# Communication_Connectors.net
KiCad netlist of a schematic drawn in Altium Designer
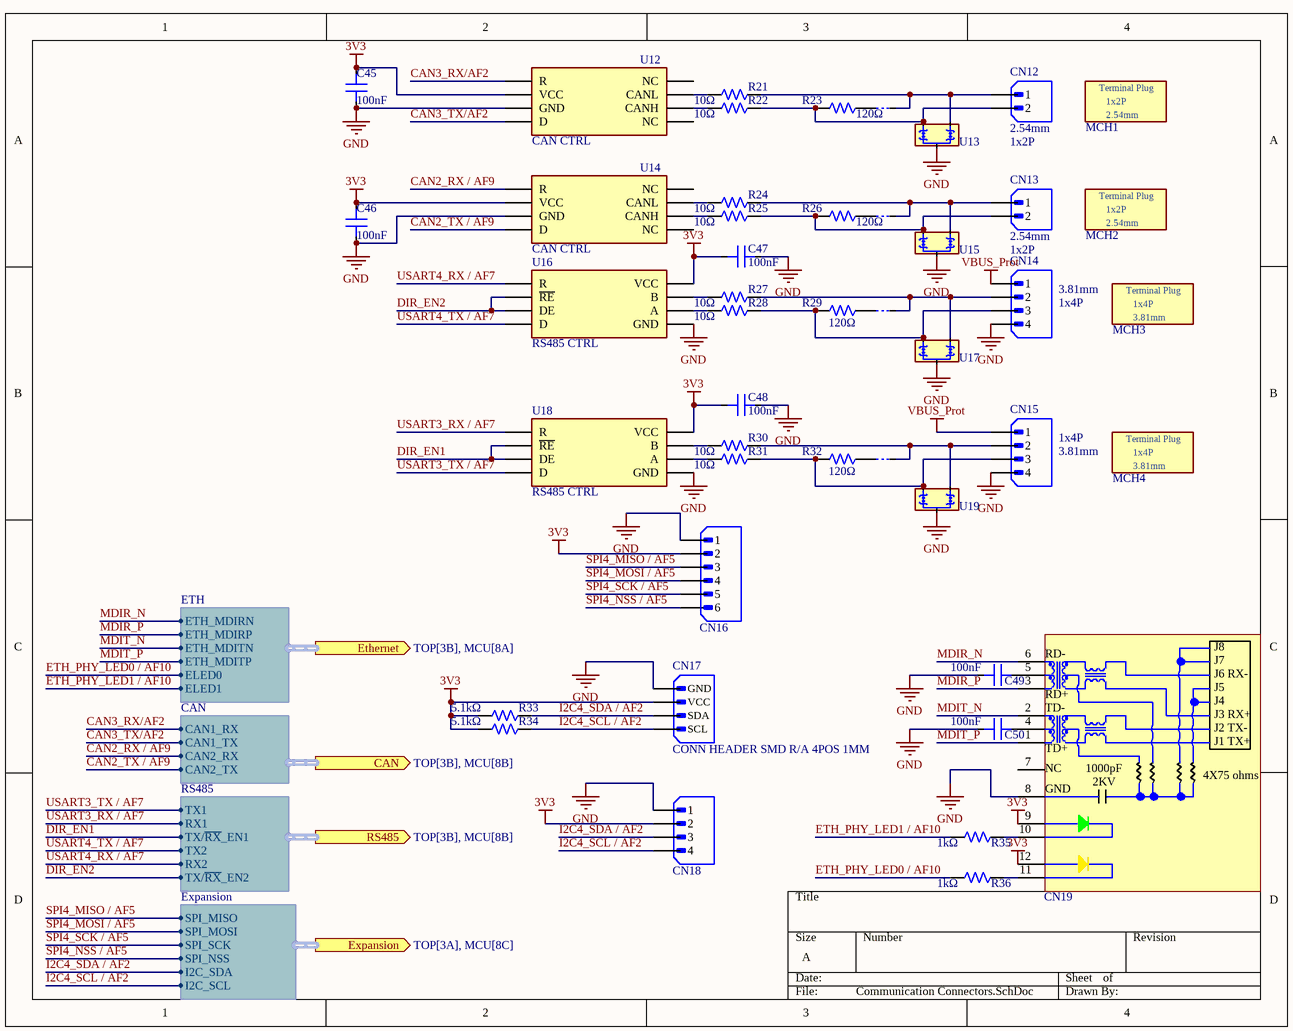
[diagram p0: Communication Connectors.SchDoc]

(export (version "E")
  (design (tool "Eeschema 10.0.6"))
  (components
    (comp (ref "C45")
      (value "CAP CER 100nF 50V X7R 0603")
      (footprint "C_0603")
      (description "100nF ±10% 50V Ceramic Capacitor X7R 0603")
      (fields
        (field (name "CAPACITANCE") "100nF")
        (field (name "MPN") "CC0603KRX7R9BB104")
        (field (name "LCSC PART #") "C14663")
      )
      (libsource (lib "Database_Libs_MICH_1") (part "CAP"))
    )
    (comp (ref "C46")
      (value "CAP CER 100nF 50V X7R 0603")
      (footprint "C_0603")
      (description "100nF ±10% 50V Ceramic Capacitor X7R 0603")
      (fields
        (field (name "CAPACITANCE") "100nF")
        (field (name "MPN") "CC0603KRX7R9BB104")
        (field (name "LCSC PART #") "C14663")
      )
      (libsource (lib "Database_Libs_MICH_1") (part "CAP"))
    )
    (comp (ref "C47")
      (value "CAP CER 100nF 50V X7R 0603")
      (footprint "C_0603")
      (description "100nF ±10% 50V Ceramic Capacitor X7R 0603")
      (fields
        (field (name "CAPACITANCE") "100nF")
        (field (name "MPN") "CC0603KRX7R9BB104")
        (field (name "LCSC PART #") "C14663")
      )
      (libsource (lib "Database_Libs_MICH_1") (part "CAP"))
    )
    (comp (ref "C48")
      (value "CAP CER 100nF 50V X7R 0603")
      (footprint "C_0603")
      (description "100nF ±10% 50V Ceramic Capacitor X7R 0603")
      (fields
        (field (name "CAPACITANCE") "100nF")
        (field (name "MPN") "CC0603KRX7R9BB104")
        (field (name "LCSC PART #") "C14663")
      )
      (libsource (lib "Database_Libs_MICH_1") (part "CAP"))
    )
    (comp (ref "C49")
      (value "CAP CER 100nF 50V X7R 0603")
      (footprint "C_0603")
      (description "100nF ±10% 50V Ceramic Capacitor X7R 0603")
      (fields
        (field (name "CAPACITANCE") "100nF")
        (field (name "MPN") "CC0603KRX7R9BB104")
        (field (name "LCSC PART #") "C14663")
      )
      (libsource (lib "Database_Libs_MICH_1") (part "CAP"))
    )
    (comp (ref "C50")
      (value "CAP CER 100nF 50V X7R 0603")
      (footprint "C_0603")
      (description "100nF ±10% 50V Ceramic Capacitor X7R 0603")
      (fields
        (field (name "CAPACITANCE") "100nF")
        (field (name "MPN") "CC0603KRX7R9BB104")
        (field (name "LCSC PART #") "C14663")
      )
      (libsource (lib "Database_Libs_MICH_1") (part "CAP"))
    )
    (comp (ref "CN12")
      (value "TERM BLOCK HDR 2POS 2.54mm")
      (footprint "TB_2P_2.54MM_PLUGGABLE_RA")
      (description "2 Position Board Side/Socket - Closed 2.54mm Pitch Right-Angle Pin")
      (fields
        (field (name "PITCH") "2.54mm")
        (field (name "POSITIONS") "1x2P")
        (field (name "MPN") "DB2ERC-2.54-2P-GN")
        (field (name "LCSC PART #") "C2927503")
      )
      (libsource (lib "Database_Libs_MICH_1") (part "TERMBLK_2"))
    )
    (comp (ref "CN13")
      (value "TERM BLOCK HDR 2POS 2.54mm")
      (footprint "TB_2P_2.54MM_PLUGGABLE_RA")
      (description "2 Position Board Side/Socket - Closed 2.54mm Pitch Right-Angle Pin")
      (fields
        (field (name "PITCH") "2.54mm")
        (field (name "POSITIONS") "1x2P")
        (field (name "MPN") "DB2ERC-2.54-2P-GN")
        (field (name "LCSC PART #") "C2927503")
      )
      (libsource (lib "Database_Libs_MICH_1") (part "TERMBLK_2"))
    )
    (comp (ref "CN14")
      (value "TERM BLOCK HDR 4POS 3.81mm")
      (footprint "TB_4P_3.81MM_PLUGGABLE_RA")
      (description "4 Position Board Side/Socket - Closed 3.81mm Pitch Right-Angle Pin")
      (fields
        (field (name "POSITIONS") "1x4P")
        (field (name "PITCH") "3.81mm")
        (field (name "MPN") "WJ15EDGRC-3.81-04P-14-00A")
        (field (name "LCSC PART #") "C7245")
      )
      (libsource (lib "Database_Libs_MICH_1") (part "TERMBLK_4"))
    )
    (comp (ref "CN15")
      (value "TERM BLOCK HDR 4POS 3.81mm")
      (footprint "TB_4P_3.81MM_PLUGGABLE_RA")
      (description "4 Position Board Side/Socket - Closed 3.81mm Pitch Right-Angle Pin")
      (fields
        (field (name "POSITIONS") "1x4P")
        (field (name "PITCH") "3.81mm")
        (field (name "MPN") "WJ15EDGRC-3.81-04P-14-00A")
        (field (name "LCSC PART #") "C7245")
      )
      (libsource (lib "Database_Libs_MICH_1") (part "TERMBLK_4"))
    )
    (comp (ref "CN16")
      (value "CONN HEADER TH 6POS 2.5mm")
      (footprint "JST_XH_6P_2.5MM_TH")
      (description "Connector Header 6 position 2.5mm Pitch 3A Through Hole -25℃~+85℃")
      (fields (field (name "MPN") "B6B-XH-A(LF)(SN)") (field (name "LCSC PART #") "C144397"))
      (libsource (lib "Database_Libs_MICH_1") (part "CONN_6"))
    )
    (comp (ref "CN17")
      (value "CONN HEADER SMD R/A 4POS 1MM")
      (footprint "JST_SH_4P_1MM_SMD_RA")
      (libsource (lib "MI_Personal_special") (part "STEMMA QT CONNECTOR"))
    )
    (comp (ref "CN18")
      (value "CONN HEADER TH 4POS 2.5mm")
      (footprint "JST_XH_4P_2.5MM_TH")
      (description "Connector Header 4 position 2.5mm Pitch 3A Through Hole -25℃~+85℃")
      (fields (field (name "MPN") "B4B-XH-A(LF)(SN)") (field (name "LCSC PART #") "C144395"))
      (libsource (lib "Database_Libs_MICH_1") (part "CONN_4"))
    )
    (comp (ref "CN19")
      (value "CONN MOD JACK RJ45 TH")
      (footprint "HR911105A")
      (description "Jack Modular Connector RJ45 Through Hole")
      (fields (field (name "MPN") "HR911105A") (field (name "LCSC PART #") "C12074"))
      (libsource (lib "Database_Libs_MICH_1") (part "HR911105A"))
    )
    (comp (ref "J2")
      (value "JUMPER SMD")
      (footprint "JUMPER SMD 3X1.5 mm")
      (libsource (lib "MI_Personal_special") (part "JUMPER SMD"))
    )
    (comp (ref "J3")
      (value "JUMPER SMD")
      (footprint "JUMPER SMD 3X1.5 mm")
      (libsource (lib "MI_Personal_special") (part "JUMPER SMD"))
    )
    (comp (ref "J4")
      (value "JUMPER SMD")
      (footprint "JUMPER SMD 3X1.5 mm")
      (libsource (lib "MI_Personal_special") (part "JUMPER SMD"))
    )
    (comp (ref "J5")
      (value "JUMPER SMD")
      (footprint "JUMPER SMD 3X1.5 mm")
      (libsource (lib "MI_Personal_special") (part "JUMPER SMD"))
    )
    (comp (ref "MCH1")
      (value "TERM BLOCK PLUG 2POS 2.54mm")
      (description "2 Position Plug 2.54mm Pitch")
      (fields (field (name "MPN") "DB2EK-2.54-2P-GN-S") (field (name "LCSC PART #") "C2927483"))
      (libsource (lib "Database_Libs_MICH_1") (part "TERMBLK_PLUG"))
    )
    (comp (ref "MCH2")
      (value "TERM BLOCK PLUG 2POS 2.54mm")
      (description "2 Position Plug 2.54mm Pitch")
      (fields (field (name "MPN") "DB2EK-2.54-2P-GN-S") (field (name "LCSC PART #") "C2927483"))
      (libsource (lib "Database_Libs_MICH_1") (part "TERMBLK_PLUG"))
    )
    (comp (ref "MCH3")
      (value "TERM BLOCK PLUG 4POS 3.81mm")
      (description "4 Position Male Plug 3.81mm Pitch")
      (fields (field (name "MPN") "WJ15EDGK-3.81-04P-14-00A") (field (name "LCSC PART #") "C7244"))
      (libsource (lib "Database_Libs_MICH_1") (part "TERMBLK_PLUG"))
    )
    (comp (ref "MCH4")
      (value "TERM BLOCK PLUG 4POS 3.81mm")
      (description "4 Position Male Plug 3.81mm Pitch")
      (fields (field (name "MPN") "WJ15EDGK-3.81-04P-14-00A") (field (name "LCSC PART #") "C7244"))
      (libsource (lib "Database_Libs_MICH_1") (part "TERMBLK_PLUG"))
    )
    (comp (ref "R21")
      (value "RES 10Ω ±5% 330mW PULSE RESIST 0603")
      (footprint "R_0603")
      (description "RES 10Ω ±5% 330mW 0603")
      (fields
        (field (name "RESISTANCE") "10Ω")
        (field (name "MPN") "CRCW060310R0JNEAHP")
        (field (name "POWER") "330mW")
      )
      (libsource (lib "Database_Libs_MICH_1") (part "RES"))
    )
    (comp (ref "R22")
      (value "RES 10Ω ±5% 330mW PULSE RESIST 0603")
      (footprint "R_0603")
      (description "RES 10Ω ±5% 330mW 0603")
      (fields
        (field (name "RESISTANCE") "10Ω")
        (field (name "MPN") "CRCW060310R0JNEAHP")
        (field (name "POWER") "330mW")
      )
      (libsource (lib "Database_Libs_MICH_1") (part "RES"))
    )
    (comp (ref "R23")
      (value "RES 120Ω ±1% 500mW 1210")
      (footprint "R_1210")
      (description "120Ω ±1% 500mW 1210 Thick Film Resistor")
      (fields
        (field (name "RESISTANCE") "120Ω")
        (field (name "MPN") "FRC1210F1200TS")
        (field (name "POWER") "500mW")
      )
      (libsource (lib "Database_Libs_MICH_1") (part "RES"))
    )
    (comp (ref "R24")
      (value "RES 10Ω ±5% 330mW PULSE RESIST 0603")
      (footprint "R_0603")
      (description "RES 10Ω ±5% 330mW 0603")
      (fields
        (field (name "RESISTANCE") "10Ω")
        (field (name "MPN") "CRCW060310R0JNEAHP")
        (field (name "POWER") "330mW")
      )
      (libsource (lib "Database_Libs_MICH_1") (part "RES"))
    )
    (comp (ref "R25")
      (value "RES 10Ω ±5% 330mW PULSE RESIST 0603")
      (footprint "R_0603")
      (description "RES 10Ω ±5% 330mW 0603")
      (fields
        (field (name "RESISTANCE") "10Ω")
        (field (name "MPN") "CRCW060310R0JNEAHP")
        (field (name "POWER") "330mW")
      )
      (libsource (lib "Database_Libs_MICH_1") (part "RES"))
    )
    (comp (ref "R26")
      (value "RES 120Ω ±1% 500mW 1210")
      (footprint "R_1210")
      (description "120Ω ±1% 500mW 1210 Thick Film Resistor")
      (fields
        (field (name "RESISTANCE") "120Ω")
        (field (name "MPN") "FRC1210F1200TS")
        (field (name "POWER") "500mW")
      )
      (libsource (lib "Database_Libs_MICH_1") (part "RES"))
    )
    (comp (ref "R27")
      (value "RES 10Ω ±5% 330mW PULSE RESIST 0603")
      (footprint "R_0603")
      (description "RES 10Ω ±5% 330mW 0603")
      (fields
        (field (name "RESISTANCE") "10Ω")
        (field (name "MPN") "CRCW060310R0JNEAHP")
        (field (name "POWER") "330mW")
      )
      (libsource (lib "Database_Libs_MICH_1") (part "RES"))
    )
    (comp (ref "R28")
      (value "RES 10Ω ±5% 330mW PULSE RESIST 0603")
      (footprint "R_0603")
      (description "RES 10Ω ±5% 330mW 0603")
      (fields
        (field (name "RESISTANCE") "10Ω")
        (field (name "MPN") "CRCW060310R0JNEAHP")
        (field (name "POWER") "330mW")
      )
      (libsource (lib "Database_Libs_MICH_1") (part "RES"))
    )
    (comp (ref "R29")
      (value "RES 120Ω ±1% 500mW 1210")
      (footprint "R_1210")
      (description "120Ω ±1% 500mW 1210 Thick Film Resistor")
      (fields
        (field (name "RESISTANCE") "120Ω")
        (field (name "MPN") "FRC1210F1200TS")
        (field (name "POWER") "500mW")
      )
      (libsource (lib "Database_Libs_MICH_1") (part "RES"))
    )
    (comp (ref "R30")
      (value "RES 10Ω ±5% 330mW PULSE RESIST 0603")
      (footprint "R_0603")
      (description "RES 10Ω ±5% 330mW 0603")
      (fields
        (field (name "RESISTANCE") "10Ω")
        (field (name "MPN") "CRCW060310R0JNEAHP")
        (field (name "POWER") "330mW")
      )
      (libsource (lib "Database_Libs_MICH_1") (part "RES"))
    )
    (comp (ref "R31")
      (value "RES 10Ω ±5% 330mW PULSE RESIST 0603")
      (footprint "R_0603")
      (description "RES 10Ω ±5% 330mW 0603")
      (fields
        (field (name "RESISTANCE") "10Ω")
        (field (name "MPN") "CRCW060310R0JNEAHP")
        (field (name "POWER") "330mW")
      )
      (libsource (lib "Database_Libs_MICH_1") (part "RES"))
    )
    (comp (ref "R32")
      (value "RES 120Ω ±1% 500mW 1210")
      (footprint "R_1210")
      (description "120Ω ±1% 500mW 1210 Thick Film Resistor")
      (fields
        (field (name "RESISTANCE") "120Ω")
        (field (name "MPN") "FRC1210F1200TS")
        (field (name "POWER") "500mW")
      )
      (libsource (lib "Database_Libs_MICH_1") (part "RES"))
    )
    (comp (ref "R33")
      (value "RES 5.1kΩ ±1% 100mW 0603")
      (footprint "R_0603")
      (description "5.1kΩ ±1% 100mW 0603 Thick Film Resistor")
      (fields
        (field (name "RESISTANCE") "5.1kΩ")
        (field (name "MPN") "0603WAF5101T5E")
        (field (name "POWER") "100mW")
      )
      (libsource (lib "Database_Libs_MICH_1") (part "RES"))
    )
    (comp (ref "R34")
      (value "RES 5.1kΩ ±1% 100mW 0603")
      (footprint "R_0603")
      (description "5.1kΩ ±1% 100mW 0603 Thick Film Resistor")
      (fields
        (field (name "RESISTANCE") "5.1kΩ")
        (field (name "MPN") "0603WAF5101T5E")
        (field (name "POWER") "100mW")
      )
      (libsource (lib "Database_Libs_MICH_1") (part "RES"))
    )
    (comp (ref "R35")
      (value "RES 1kΩ ±1% 100mW 0603")
      (footprint "R_0603")
      (description "1kΩ ±1% 100mW 0603 Thick Film Resistor")
      (fields
        (field (name "RESISTANCE") "1kΩ")
        (field (name "MPN") "0603WAF1001T5E")
        (field (name "POWER") "100mW")
      )
      (libsource (lib "Database_Libs_MICH_1") (part "RES"))
    )
    (comp (ref "R36")
      (value "RES 1kΩ ±1% 100mW 0603")
      (footprint "R_0603")
      (description "1kΩ ±1% 100mW 0603 Thick Film Resistor")
      (fields
        (field (name "RESISTANCE") "1kΩ")
        (field (name "MPN") "0603WAF1001T5E")
        (field (name "POWER") "100mW")
      )
      (libsource (lib "Database_Libs_MICH_1") (part "RES"))
    )
    (comp (ref "U12")
      (value "CAN CTRL")
      (footprint "SOIC-8")
      (description "3.3-V CAN TRANSCEIVERS")
      (fields (field (name "LCSC PART #") "C12084") (field (name "MANUFACTURER") "TI"))
      (libsource (lib "Database_Libs_MICH_1") (part "SN65HVD230DR"))
    )
    (comp (ref "U13")
      (value "ESD DIODE 24VWM 70VC SOT-23")
      (footprint "SOT-23")
      (description "70VC Clamp 3A@8/20us Ipp ESD DIODE SOT-23")
      (fields (field (name "MPN") "PESD1CAN,215") (field (name "LCSC PART #") "C15771"))
      (libsource (lib "Database_Libs_MICH_1") (part "DIODE_TVS_2CH_SOT-23"))
    )
    (comp (ref "U14")
      (value "CAN CTRL")
      (footprint "SOIC-8")
      (description "3.3-V CAN TRANSCEIVERS")
      (fields (field (name "LCSC PART #") "C12084") (field (name "MANUFACTURER") "TI"))
      (libsource (lib "Database_Libs_MICH_1") (part "SN65HVD230DR"))
    )
    (comp (ref "U15")
      (value "ESD DIODE 24VWM 70VC SOT-23")
      (footprint "SOT-23")
      (description "70VC Clamp 3A@8/20us Ipp ESD DIODE SOT-23")
      (fields (field (name "MPN") "PESD1CAN,215") (field (name "LCSC PART #") "C15771"))
      (libsource (lib "Database_Libs_MICH_1") (part "DIODE_TVS_2CH_SOT-23"))
    )
    (comp (ref "U16")
      (value "RS485 CTRL")
      (footprint "SOIC-8")
      (description "SN65HVD72, SN65HVD75, SN65HVD78 3.3V Power Supply RS-485 with IEC ESD Protection")
      (fields (field (name "MPN") "SN65HVD75DR") (field (name "LCSC PART #") "C57928"))
      (libsource (lib "Database_Libs_MICH_1") (part "SN65HVD75DR"))
    )
    (comp (ref "U17")
      (value "ESD DIODE 12VWM 7VWM 26VC 14VC SOT-23")
      (footprint "SOT-23")
      (description "26VC 14VC Clamp ESD DIODE SOT-23")
      (fields (field (name "MPN") "CDSOT23-SM712") (field (name "LCSC PART #") "C404012"))
      (libsource (lib "Database_Libs_MICH_1") (part "DIODE_TVS_2CH_SOT-23"))
    )
    (comp (ref "U18")
      (value "RS485 CTRL")
      (footprint "SOIC-8")
      (description "SN65HVD72, SN65HVD75, SN65HVD78 3.3V Power Supply RS-485 with IEC ESD Protection")
      (fields (field (name "MPN") "SN65HVD75DR") (field (name "LCSC PART #") "C57928"))
      (libsource (lib "Database_Libs_MICH_1") (part "SN65HVD75DR"))
    )
    (comp (ref "U19")
      (value "ESD DIODE 12VWM 7VWM 26VC 14VC SOT-23")
      (footprint "SOT-23")
      (description "26VC 14VC Clamp ESD DIODE SOT-23")
      (fields (field (name "MPN") "CDSOT23-SM712") (field (name "LCSC PART #") "C404012"))
      (libsource (lib "Database_Libs_MICH_1") (part "DIODE_TVS_2CH_SOT-23"))
    )
  )
  (nets
    (net (code "5") (name "/CAN2_RX {slash} AF9") (class "Default")
      (node (ref "U14") (pin "4") (pinfunction "R_4") (pintype "passive"))
    )
    (net (code "6") (name "/CAN2_TX {slash} AF9") (class "Default")
      (node (ref "U14") (pin "1") (pinfunction "D_1") (pintype "passive"))
    )
    (net (code "7") (name "/CAN3_RX{slash}AF2") (class "Default")
      (node (ref "U12") (pin "4") (pinfunction "R_4") (pintype "passive"))
    )
    (net (code "8") (name "/CAN3_TX{slash}AF2") (class "Default")
      (node (ref "U12") (pin "1") (pinfunction "D_1") (pintype "passive"))
    )
    (net (code "9") (name "/DIR_EN1") (class "Default")
      (node (ref "U18") (pin "2") (pinfunction "~{RE}_2") (pintype "passive"))
      (node (ref "U18") (pin "3") (pinfunction "DE_3") (pintype "passive"))
    )
    (net (code "10") (name "/DIR_EN2") (class "Default")
      (node (ref "U16") (pin "2") (pinfunction "~{RE}_2") (pintype "passive"))
      (node (ref "U16") (pin "3") (pinfunction "DE_3") (pintype "passive"))
    )
    (net (code "11") (name "/ETH_PHY_LED0 {slash} AF10") (class "Default")
      (node (ref "R36") (pin "1") (pinfunction "1_1") (pintype "passive"))
    )
    (net (code "12") (name "/ETH_PHY_LED1 {slash} AF10") (class "Default")
      (node (ref "R35") (pin "1") (pinfunction "1_1") (pintype "passive"))
    )
    (net (code "13") (name "/I2C4_SCL {slash} AF2") (class "Default")
      (node (ref "CN17") (pin "4") (pinfunction "SCL_4") (pintype "passive"))
      (node (ref "CN18") (pin "4") (pinfunction "4_4") (pintype "passive"))
      (node (ref "R34") (pin "2") (pinfunction "2_2") (pintype "passive"))
    )
    (net (code "14") (name "/I2C4_SDA {slash} AF2") (class "Default")
      (node (ref "CN17") (pin "3") (pinfunction "SDA_3") (pintype "passive"))
      (node (ref "CN18") (pin "3") (pinfunction "3_3") (pintype "passive"))
      (node (ref "R33") (pin "2") (pinfunction "2_2") (pintype "passive"))
    )
    (net (code "15") (name "/MDIR_N") (class "Default") (node (ref "CN19") (pin "6") (pintype "passive")))
    (net (code "16") (name "/MDIR_P") (class "Default") (node (ref "CN19") (pin "3") (pintype "passive")))
    (net (code "17") (name "/MDIT_N") (class "Default") (node (ref "CN19") (pin "2") (pintype "passive")))
    (net (code "18") (name "/MDIT_P") (class "Default") (node (ref "CN19") (pin "1") (pintype "passive")))
    (net (code "19") (name "/SPI4_MISO {slash} AF5") (class "Default")
      (node (ref "CN16") (pin "3") (pinfunction "3_3") (pintype "passive"))
    )
    (net (code "20") (name "/SPI4_MOSI {slash} AF5") (class "Default")
      (node (ref "CN16") (pin "4") (pinfunction "4_4") (pintype "passive"))
    )
    (net (code "21") (name "/SPI4_NSS {slash} AF5") (class "Default")
      (node (ref "CN16") (pin "6") (pinfunction "6_6") (pintype "passive"))
    )
    (net (code "22") (name "/SPI4_SCK {slash} AF5") (class "Default")
      (node (ref "CN16") (pin "5") (pinfunction "5_5") (pintype "passive"))
    )
    (net (code "23") (name "/USART3_RX {slash} AF7") (class "Default")
      (node (ref "U18") (pin "1") (pinfunction "R_1") (pintype "passive"))
    )
    (net (code "24") (name "/USART3_TX {slash} AF7") (class "Default")
      (node (ref "U18") (pin "4") (pinfunction "D_4") (pintype "passive"))
    )
    (net (code "25") (name "/USART4_RX {slash} AF7") (class "Default")
      (node (ref "U16") (pin "1") (pinfunction "R_1") (pintype "passive"))
    )
    (net (code "26") (name "/USART4_TX {slash} AF7") (class "Default")
      (node (ref "U16") (pin "4") (pinfunction "D_4") (pintype "passive"))
    )
    (net (code "31") (name "3V3") (class "Default")
      (node (ref "C45") (pin "2") (pinfunction "2_2") (pintype "passive"))
      (node (ref "C46") (pin "2") (pinfunction "2_2") (pintype "passive"))
      (node (ref "C47") (pin "1") (pinfunction "1_1") (pintype "passive"))
      (node (ref "C48") (pin "1") (pinfunction "1_1") (pintype "passive"))
      (node (ref "CN16") (pin "2") (pinfunction "2_2") (pintype "passive"))
      (node (ref "CN17") (pin "2") (pinfunction "VCC_2") (pintype "passive"))
      (node (ref "CN18") (pin "2") (pinfunction "2_2") (pintype "passive"))
      (node (ref "CN19") (pin "12") (pintype "passive"))
      (node (ref "CN19") (pin "9") (pintype "passive"))
      (node (ref "R33") (pin "1") (pinfunction "1_1") (pintype "passive"))
      (node (ref "R34") (pin "1") (pinfunction "1_1") (pintype "passive"))
      (node (ref "U12") (pin "3") (pinfunction "VCC_3") (pintype "passive"))
      (node (ref "U14") (pin "3") (pinfunction "VCC_3") (pintype "passive"))
      (node (ref "U16") (pin "8") (pinfunction "VCC_8") (pintype "passive"))
      (node (ref "U18") (pin "8") (pinfunction "VCC_8") (pintype "passive"))
    )
    (net (code "32") (name "GND") (class "Default")
      (node (ref "C45") (pin "1") (pinfunction "1_1") (pintype "passive"))
      (node (ref "C46") (pin "1") (pinfunction "1_1") (pintype "passive"))
      (node (ref "C47") (pin "2") (pinfunction "2_2") (pintype "passive"))
      (node (ref "C48") (pin "2") (pinfunction "2_2") (pintype "passive"))
      (node (ref "C49") (pin "2") (pinfunction "2_2") (pintype "passive"))
      (node (ref "C50") (pin "2") (pinfunction "2_2") (pintype "passive"))
      (node (ref "CN14") (pin "4") (pinfunction "4_4") (pintype "passive"))
      (node (ref "CN15") (pin "4") (pinfunction "4_4") (pintype "passive"))
      (node (ref "CN16") (pin "1") (pinfunction "1_1") (pintype "passive"))
      (node (ref "CN17") (pin "1") (pinfunction "GND_1") (pintype "passive"))
      (node (ref "CN18") (pin "1") (pinfunction "1_1") (pintype "passive"))
      (node (ref "CN19") (pin "8") (pintype "passive"))
      (node (ref "U12") (pin "2") (pinfunction "GND_2") (pintype "passive"))
      (node (ref "U13") (pin "3") (pinfunction "3_3") (pintype "passive"))
      (node (ref "U14") (pin "2") (pinfunction "GND_2") (pintype "passive"))
      (node (ref "U15") (pin "3") (pinfunction "3_3") (pintype "passive"))
      (node (ref "U16") (pin "5") (pinfunction "GND_5") (pintype "passive"))
      (node (ref "U17") (pin "3") (pinfunction "3_3") (pintype "passive"))
      (node (ref "U18") (pin "5") (pinfunction "GND_5") (pintype "passive"))
      (node (ref "U19") (pin "3") (pinfunction "3_3") (pintype "passive"))
    )
    (net (code "33") (name "Net-(C49-Pad1)") (class "Default")
      (node (ref "C49") (pin "1") (pinfunction "1_1") (pintype "passive"))
      (node (ref "CN19") (pin "5") (pintype "passive"))
    )
    (net (code "34") (name "Net-(C50-Pad1)") (class "Default")
      (node (ref "C50") (pin "1") (pinfunction "1_1") (pintype "passive"))
      (node (ref "CN19") (pin "4") (pintype "passive"))
    )
    (net (code "35") (name "Net-(CN12-Pad1)") (class "Default")
      (node (ref "CN12") (pin "1") (pinfunction "1_1") (pintype "passive"))
      (node (ref "J2") (pin "1") (pinfunction "1_1") (pintype "passive"))
      (node (ref "R21") (pin "2") (pinfunction "2_2") (pintype "passive"))
      (node (ref "U13") (pin "1") (pinfunction "1_1") (pintype "passive"))
    )
    (net (code "36") (name "Net-(CN12-Pad2)") (class "Default")
      (node (ref "CN12") (pin "2") (pinfunction "2_2") (pintype "passive"))
      (node (ref "R22") (pin "2") (pinfunction "2_2") (pintype "passive"))
      (node (ref "R23") (pin "1") (pinfunction "1_1") (pintype "passive"))
      (node (ref "U13") (pin "2") (pinfunction "2_2") (pintype "passive"))
    )
    (net (code "37") (name "Net-(CN13-Pad1)") (class "Default")
      (node (ref "CN13") (pin "1") (pinfunction "1_1") (pintype "passive"))
      (node (ref "J3") (pin "1") (pinfunction "1_1") (pintype "passive"))
      (node (ref "R24") (pin "2") (pinfunction "2_2") (pintype "passive"))
      (node (ref "U15") (pin "1") (pinfunction "1_1") (pintype "passive"))
    )
    (net (code "38") (name "Net-(CN13-Pad2)") (class "Default")
      (node (ref "CN13") (pin "2") (pinfunction "2_2") (pintype "passive"))
      (node (ref "R25") (pin "2") (pinfunction "2_2") (pintype "passive"))
      (node (ref "R26") (pin "1") (pinfunction "1_1") (pintype "passive"))
      (node (ref "U15") (pin "2") (pinfunction "2_2") (pintype "passive"))
    )
    (net (code "39") (name "Net-(CN14-Pad2)") (class "Default")
      (node (ref "CN14") (pin "2") (pinfunction "2_2") (pintype "passive"))
      (node (ref "J4") (pin "1") (pinfunction "1_1") (pintype "passive"))
      (node (ref "R27") (pin "2") (pinfunction "2_2") (pintype "passive"))
      (node (ref "U17") (pin "1") (pinfunction "1_1") (pintype "passive"))
    )
    (net (code "40") (name "Net-(CN14-Pad3)") (class "Default")
      (node (ref "CN14") (pin "3") (pinfunction "3_3") (pintype "passive"))
      (node (ref "R28") (pin "2") (pinfunction "2_2") (pintype "passive"))
      (node (ref "R29") (pin "1") (pinfunction "1_1") (pintype "passive"))
      (node (ref "U17") (pin "2") (pinfunction "2_2") (pintype "passive"))
    )
    (net (code "41") (name "Net-(CN15-Pad2)") (class "Default")
      (node (ref "CN15") (pin "2") (pinfunction "2_2") (pintype "passive"))
      (node (ref "J5") (pin "1") (pinfunction "1_1") (pintype "passive"))
      (node (ref "R30") (pin "2") (pinfunction "2_2") (pintype "passive"))
      (node (ref "U19") (pin "1") (pinfunction "1_1") (pintype "passive"))
    )
    (net (code "42") (name "Net-(CN15-Pad3)") (class "Default")
      (node (ref "CN15") (pin "3") (pinfunction "3_3") (pintype "passive"))
      (node (ref "R31") (pin "2") (pinfunction "2_2") (pintype "passive"))
      (node (ref "R32") (pin "1") (pinfunction "1_1") (pintype "passive"))
      (node (ref "U19") (pin "2") (pinfunction "2_2") (pintype "passive"))
    )
    (net (code "43") (name "Net-(CN19-Pad10)") (class "Default")
      (node (ref "CN19") (pin "10") (pintype "passive"))
      (node (ref "R35") (pin "2") (pinfunction "2_2") (pintype "passive"))
    )
    (net (code "44") (name "Net-(CN19-Pad11)") (class "Default")
      (node (ref "CN19") (pin "11") (pintype "passive"))
      (node (ref "R36") (pin "2") (pinfunction "2_2") (pintype "passive"))
    )
    (net (code "45") (name "Net-(J2-G)") (class "Default")
      (node (ref "J2") (pin "2") (pinfunction "G_2") (pintype "passive"))
      (node (ref "R23") (pin "2") (pinfunction "2_2") (pintype "passive"))
    )
    (net (code "46") (name "Net-(J3-G)") (class "Default")
      (node (ref "J3") (pin "2") (pinfunction "G_2") (pintype "passive"))
      (node (ref "R26") (pin "2") (pinfunction "2_2") (pintype "passive"))
    )
    (net (code "47") (name "Net-(J4-G)") (class "Default")
      (node (ref "J4") (pin "2") (pinfunction "G_2") (pintype "passive"))
      (node (ref "R29") (pin "2") (pinfunction "2_2") (pintype "passive"))
    )
    (net (code "48") (name "Net-(J5-G)") (class "Default")
      (node (ref "J5") (pin "2") (pinfunction "G_2") (pintype "passive"))
      (node (ref "R32") (pin "2") (pinfunction "2_2") (pintype "passive"))
    )
    (net (code "49") (name "Net-(U12-CANH)") (class "Default")
      (node (ref "R22") (pin "1") (pinfunction "1_1") (pintype "passive"))
      (node (ref "U12") (pin "7") (pinfunction "CANH_7") (pintype "passive"))
    )
    (net (code "50") (name "Net-(U12-CANL)") (class "Default")
      (node (ref "R21") (pin "1") (pinfunction "1_1") (pintype "passive"))
      (node (ref "U12") (pin "6") (pinfunction "CANL_6") (pintype "passive"))
    )
    (net (code "51") (name "Net-(U14-CANH)") (class "Default")
      (node (ref "R25") (pin "1") (pinfunction "1_1") (pintype "passive"))
      (node (ref "U14") (pin "7") (pinfunction "CANH_7") (pintype "passive"))
    )
    (net (code "52") (name "Net-(U14-CANL)") (class "Default")
      (node (ref "R24") (pin "1") (pinfunction "1_1") (pintype "passive"))
      (node (ref "U14") (pin "6") (pinfunction "CANL_6") (pintype "passive"))
    )
    (net (code "53") (name "Net-(U16-A)") (class "Default")
      (node (ref "R28") (pin "1") (pinfunction "1_1") (pintype "passive"))
      (node (ref "U16") (pin "6") (pinfunction "A_6") (pintype "passive"))
    )
    (net (code "54") (name "Net-(U16-B)") (class "Default")
      (node (ref "R27") (pin "1") (pinfunction "1_1") (pintype "passive"))
      (node (ref "U16") (pin "7") (pinfunction "B_7") (pintype "passive"))
    )
    (net (code "55") (name "Net-(U18-A)") (class "Default")
      (node (ref "R31") (pin "1") (pinfunction "1_1") (pintype "passive"))
      (node (ref "U18") (pin "6") (pinfunction "A_6") (pintype "passive"))
    )
    (net (code "56") (name "Net-(U18-B)") (class "Default")
      (node (ref "R30") (pin "1") (pinfunction "1_1") (pintype "passive"))
      (node (ref "U18") (pin "7") (pinfunction "B_7") (pintype "passive"))
    )
    (net (code "57") (name "VBUS_Prot") (class "Default")
      (node (ref "CN14") (pin "1") (pinfunction "1_1") (pintype "passive"))
      (node (ref "CN15") (pin "1") (pinfunction "1_1") (pintype "passive"))
    )
    (net (code "58") (name "unconnected-(CN19-Pad7)") (class "Default")
      (node (ref "CN19") (pin "7") (pintype "passive"))
    )
    (net (code "59") (name "unconnected-(U12-NC-Pad5)") (class "Default")
      (node (ref "U12") (pin "5") (pinfunction "NC_5") (pintype "passive"))
    )
    (net (code "60") (name "unconnected-(U12-NC-Pad8)") (class "Default")
      (node (ref "U12") (pin "8") (pinfunction "NC_8") (pintype "passive"))
    )
    (net (code "61") (name "unconnected-(U14-NC-Pad5)") (class "Default")
      (node (ref "U14") (pin "5") (pinfunction "NC_5") (pintype "passive"))
    )
    (net (code "62") (name "unconnected-(U14-NC-Pad8)") (class "Default")
      (node (ref "U14") (pin "8") (pinfunction "NC_8") (pintype "passive"))
    )
  )
)
